# nanopi-black2-shield.net
KiCad netlist of a schematic drawn in EAGLE
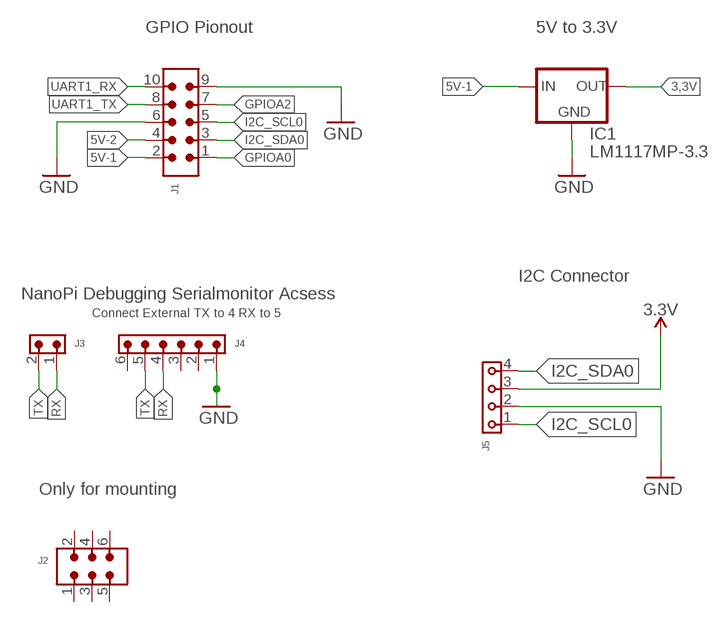
[diagram p0: schematic, sheet 1]

(export (version "E")
  (design (tool "Eeschema 10.0.6"))
  (components
    (comp (ref "IC1")
      (value "LM1117MP-3.3")
      (footprint "eagle-import:SOT223")
      (fields (field (name "MF") "Texas Instruments"))
      (libsource (lib "eagle-import") (part "LM1117?-MP3.3"))
    )
    (comp (ref "J1")
      (value "6130XX21121_61301021121")
      (footprint "eagle-import:61301021121")
      (libsource (lib "eagle-import") (part "6130XX21121_61301021121"))
    )
    (comp (ref "J2")
      (value "6130XX21121_61300621121")
      (footprint "eagle-import:61300621121")
      (libsource (lib "eagle-import") (part "6130XX21121_61300621121"))
    )
    (comp (ref "J3")
      (value "6130XX11021_61300211021")
      (footprint "eagle-import:61300211021")
      (libsource (lib "eagle-import") (part "6130XX11021_61300211021"))
    )
    (comp (ref "J4")
      (value "6130XX11021_61300611021")
      (footprint "eagle-import:61300611021")
      (libsource (lib "eagle-import") (part "6130XX11021_61300611021"))
    )
    (comp (ref "J5")
      (value "6130XX11821_61300411821")
      (footprint "eagle-import:61300411821")
      (libsource (lib "eagle-import") (part "6130XX11821_61300411821"))
    )
  )
  (nets
    (net (code "1") (name "3,3V") (class "Default")
      (node (ref "IC1") (pin "2") (pinfunction "OUT_2") (pintype "passive"))
      (node (ref "IC1") (pin "4") (pinfunction "OUT_4") (pintype "passive"))
    )
    (net (code "2") (name "3.3V") (class "Default")
      (node (ref "J5") (pin "3") (pinfunction "3_3") (pintype "passive"))
    )
    (net (code "3") (name "5V-1") (class "Default")
      (node (ref "IC1") (pin "3") (pinfunction "IN_3") (pintype "input"))
      (node (ref "J1") (pin "2") (pinfunction "2_2") (pintype "passive"))
    )
    (net (code "4") (name "5V-2") (class "Default")
      (node (ref "J1") (pin "4") (pinfunction "4_4") (pintype "passive"))
    )
    (net (code "5") (name "GND") (class "Default")
      (node (ref "IC1") (pin "1") (pinfunction "GND_1") (pintype "input"))
      (node (ref "J1") (pin "6") (pinfunction "6_6") (pintype "passive"))
      (node (ref "J1") (pin "9") (pinfunction "9_9") (pintype "passive"))
      (node (ref "J4") (pin "1") (pinfunction "1_1") (pintype "passive"))
      (node (ref "J5") (pin "2") (pinfunction "2_2") (pintype "passive"))
    )
    (net (code "6") (name "GPIOA0") (class "Default")
      (node (ref "J1") (pin "1") (pinfunction "1_1") (pintype "passive"))
    )
    (net (code "7") (name "GPIOA2") (class "Default")
      (node (ref "J1") (pin "7") (pinfunction "7_7") (pintype "passive"))
    )
    (net (code "8") (name "I2C_SCL0") (class "Default")
      (node (ref "J1") (pin "5") (pinfunction "5_5") (pintype "passive"))
      (node (ref "J5") (pin "1") (pinfunction "1_1") (pintype "passive"))
    )
    (net (code "9") (name "I2C_SDA0") (class "Default")
      (node (ref "J1") (pin "3") (pinfunction "3_3") (pintype "passive"))
      (node (ref "J5") (pin "4") (pinfunction "4_4") (pintype "passive"))
    )
    (net (code "10") (name "RX") (class "Default")
      (node (ref "J3") (pin "1") (pinfunction "1_1") (pintype "passive"))
      (node (ref "J4") (pin "4") (pinfunction "4_4") (pintype "passive"))
    )
    (net (code "11") (name "TX") (class "Default")
      (node (ref "J3") (pin "2") (pinfunction "2_2") (pintype "passive"))
      (node (ref "J4") (pin "5") (pinfunction "5_5") (pintype "passive"))
    )
    (net (code "12") (name "UART1_RX") (class "Default")
      (node (ref "J1") (pin "10") (pinfunction "10_10") (pintype "passive"))
    )
    (net (code "13") (name "UART1_TX") (class "Default")
      (node (ref "J1") (pin "8") (pinfunction "8_8") (pintype "passive"))
    )
    (net (code "14") (name "unconnected-(J2-Pad1)") (class "Default")
      (node (ref "J2") (pin "1") (pinfunction "1_1") (pintype "passive"))
    )
    (net (code "15") (name "unconnected-(J2-Pad2)") (class "Default")
      (node (ref "J2") (pin "2") (pinfunction "2_2") (pintype "passive"))
    )
    (net (code "16") (name "unconnected-(J2-Pad3)") (class "Default")
      (node (ref "J2") (pin "3") (pinfunction "3_3") (pintype "passive"))
    )
    (net (code "17") (name "unconnected-(J2-Pad4)") (class "Default")
      (node (ref "J2") (pin "4") (pinfunction "4_4") (pintype "passive"))
    )
    (net (code "18") (name "unconnected-(J2-Pad5)") (class "Default")
      (node (ref "J2") (pin "5") (pinfunction "5_5") (pintype "passive"))
    )
    (net (code "19") (name "unconnected-(J2-Pad6)") (class "Default")
      (node (ref "J2") (pin "6") (pinfunction "6_6") (pintype "passive"))
    )
    (net (code "20") (name "unconnected-(J4-Pad2)") (class "Default")
      (node (ref "J4") (pin "2") (pinfunction "2_2") (pintype "passive"))
    )
    (net (code "21") (name "unconnected-(J4-Pad3)") (class "Default")
      (node (ref "J4") (pin "3") (pinfunction "3_3") (pintype "passive"))
    )
    (net (code "22") (name "unconnected-(J4-Pad6)") (class "Default")
      (node (ref "J4") (pin "6") (pinfunction "6_6") (pintype "passive"))
    )
  )
)
